# inmux.net
KiCad netlist of a schematic drawn in Altium Designer
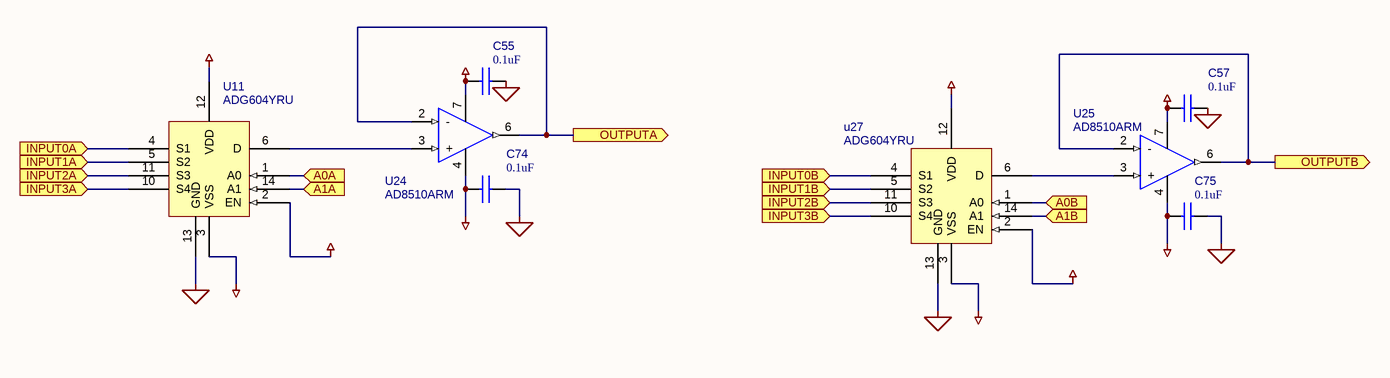
[diagram p0: inmux.SCHDOC]

(export (version "E")
  (design (tool "Eeschema 10.0.6"))
  (components
    (comp (ref "C55")
      (value "0.1uF")
      (footprint "0603")
      (description "Standard Capacitor")
      (fields (field (name "Comment") "CAPACITOR"))
      (libsource (lib "parts") (part "CAPACITOR"))
    )
    (comp (ref "C57")
      (value "0.1uF")
      (footprint "0603")
      (description "Standard Capacitor")
      (fields (field (name "Comment") "CAPACITOR"))
      (libsource (lib "parts") (part "CAPACITOR"))
    )
    (comp (ref "C74")
      (value "0.1uF")
      (footprint "0603")
      (description "Standard Capacitor")
      (fields (field (name "Comment") "CAPACITOR"))
      (libsource (lib "parts") (part "CAPACITOR"))
    )
    (comp (ref "C75")
      (value "0.1uF")
      (footprint "0603")
      (description "Standard Capacitor")
      (fields (field (name "Comment") "CAPACITOR"))
      (libsource (lib "parts") (part "CAPACITOR"))
    )
    (comp (ref "U11")
      (value "ADG604YRU")
      (footprint "SSO-G14/X.4")
      (description "1 pC Charge Injection 100pA leakage CMOS 4-channel mux")
      (libsource (lib "parts") (part "ADG604"))
    )
    (comp (ref "U24")
      (value "AD8510ARM")
      (footprint "TSSO3X5-G8/X.4")
      (description "Precision Low Noise, Low Input Bias Current Operational Amplifier")
      (libsource (lib "parts") (part "OP1177"))
    )
    (comp (ref "U25")
      (value "AD8510ARM")
      (footprint "TSSO3X5-G8/X.4")
      (description "Precision Low Noise, Low Input Bias Current Operational Amplifier")
      (libsource (lib "parts") (part "OP1177"))
    )
    (comp (ref "u27")
      (value "ADG604YRU")
      (footprint "SSO-G14/X.4")
      (description "1 pC Charge Injection 100pA leakage CMOS 4-channel mux")
      (libsource (lib "parts") (part "ADG604"))
    )
  )
  (nets
    (net (code "1") (name "/A0A") (class "Default")
      (node (ref "U11") (pin "1") (pinfunction "A0_1") (pintype "input"))
    )
    (net (code "2") (name "/A0B") (class "Default")
      (node (ref "u27") (pin "1") (pinfunction "A0_1") (pintype "input"))
    )
    (net (code "3") (name "/A1A") (class "Default")
      (node (ref "U11") (pin "14") (pinfunction "A1_14") (pintype "input"))
    )
    (net (code "4") (name "/A1B") (class "Default")
      (node (ref "u27") (pin "14") (pinfunction "A1_14") (pintype "input"))
    )
    (net (code "5") (name "/INPUT0A") (class "Default")
      (node (ref "U11") (pin "4") (pinfunction "S1_4") (pintype "passive"))
    )
    (net (code "6") (name "/INPUT0B") (class "Default")
      (node (ref "u27") (pin "4") (pinfunction "S1_4") (pintype "passive"))
    )
    (net (code "7") (name "/INPUT1A") (class "Default")
      (node (ref "U11") (pin "5") (pinfunction "S2_5") (pintype "passive"))
    )
    (net (code "8") (name "/INPUT1B") (class "Default")
      (node (ref "u27") (pin "5") (pinfunction "S2_5") (pintype "passive"))
    )
    (net (code "9") (name "/INPUT2A") (class "Default")
      (node (ref "U11") (pin "11") (pinfunction "S3_11") (pintype "passive"))
    )
    (net (code "10") (name "/INPUT2B") (class "Default")
      (node (ref "u27") (pin "11") (pinfunction "S3_11") (pintype "passive"))
    )
    (net (code "11") (name "/INPUT3A") (class "Default")
      (node (ref "U11") (pin "10") (pinfunction "S4_10") (pintype "passive"))
    )
    (net (code "12") (name "/INPUT3B") (class "Default")
      (node (ref "u27") (pin "10") (pinfunction "S4_10") (pintype "passive"))
    )
    (net (code "13") (name "/OUTPUTA") (class "Default")
      (node (ref "U24") (pin "2") (pinfunction "-_2") (pintype "input"))
      (node (ref "U24") (pin "6") (pinfunction "Out_6") (pintype "output"))
    )
    (net (code "14") (name "/OUTPUTB") (class "Default")
      (node (ref "U25") (pin "2") (pinfunction "-_2") (pintype "input"))
      (node (ref "U25") (pin "6") (pinfunction "Out_6") (pintype "output"))
    )
    (net (code "15") (name "AGND") (class "Default")
      (node (ref "C55") (pin "2") (pintype "passive"))
      (node (ref "C57") (pin "2") (pintype "passive"))
      (node (ref "C74") (pin "2") (pintype "passive"))
      (node (ref "C75") (pin "2") (pintype "passive"))
      (node (ref "U11") (pin "13") (pinfunction "GND_13") (pintype "power_in"))
      (node (ref "u27") (pin "13") (pinfunction "GND_13") (pintype "power_in"))
    )
    (net (code "16") (name "AVDD") (class "Default")
      (node (ref "C55") (pin "1") (pintype "passive"))
      (node (ref "C57") (pin "1") (pintype "passive"))
      (node (ref "U11") (pin "12") (pinfunction "VDD_12") (pintype "power_in"))
      (node (ref "U11") (pin "2") (pinfunction "EN_2") (pintype "input"))
      (node (ref "U24") (pin "7") (pinfunction "+Vs_7") (pintype "power_in"))
      (node (ref "U25") (pin "7") (pinfunction "+Vs_7") (pintype "power_in"))
      (node (ref "u27") (pin "12") (pinfunction "VDD_12") (pintype "power_in"))
      (node (ref "u27") (pin "2") (pinfunction "EN_2") (pintype "input"))
    )
    (net (code "17") (name "AVSS") (class "Default")
      (node (ref "C74") (pin "1") (pintype "passive"))
      (node (ref "C75") (pin "1") (pintype "passive"))
      (node (ref "U11") (pin "3") (pinfunction "VSS_3") (pintype "power_in"))
      (node (ref "U24") (pin "4") (pinfunction "-Vs_4") (pintype "power_in"))
      (node (ref "U25") (pin "4") (pinfunction "-Vs_4") (pintype "power_in"))
      (node (ref "u27") (pin "3") (pinfunction "VSS_3") (pintype "power_in"))
    )
    (net (code "18") (name "Net-(U11-D)") (class "Default")
      (node (ref "U11") (pin "6") (pinfunction "D_6") (pintype "passive"))
      (node (ref "U24") (pin "3") (pinfunction "+_3") (pintype "input"))
    )
    (net (code "19") (name "Net-(U25-+)") (class "Default")
      (node (ref "U25") (pin "3") (pinfunction "+_3") (pintype "input"))
      (node (ref "u27") (pin "6") (pinfunction "D_6") (pintype "passive"))
    )
  )
)
